# Schematic_RX.net
KiCad netlist of a schematic drawn in Altium Designer
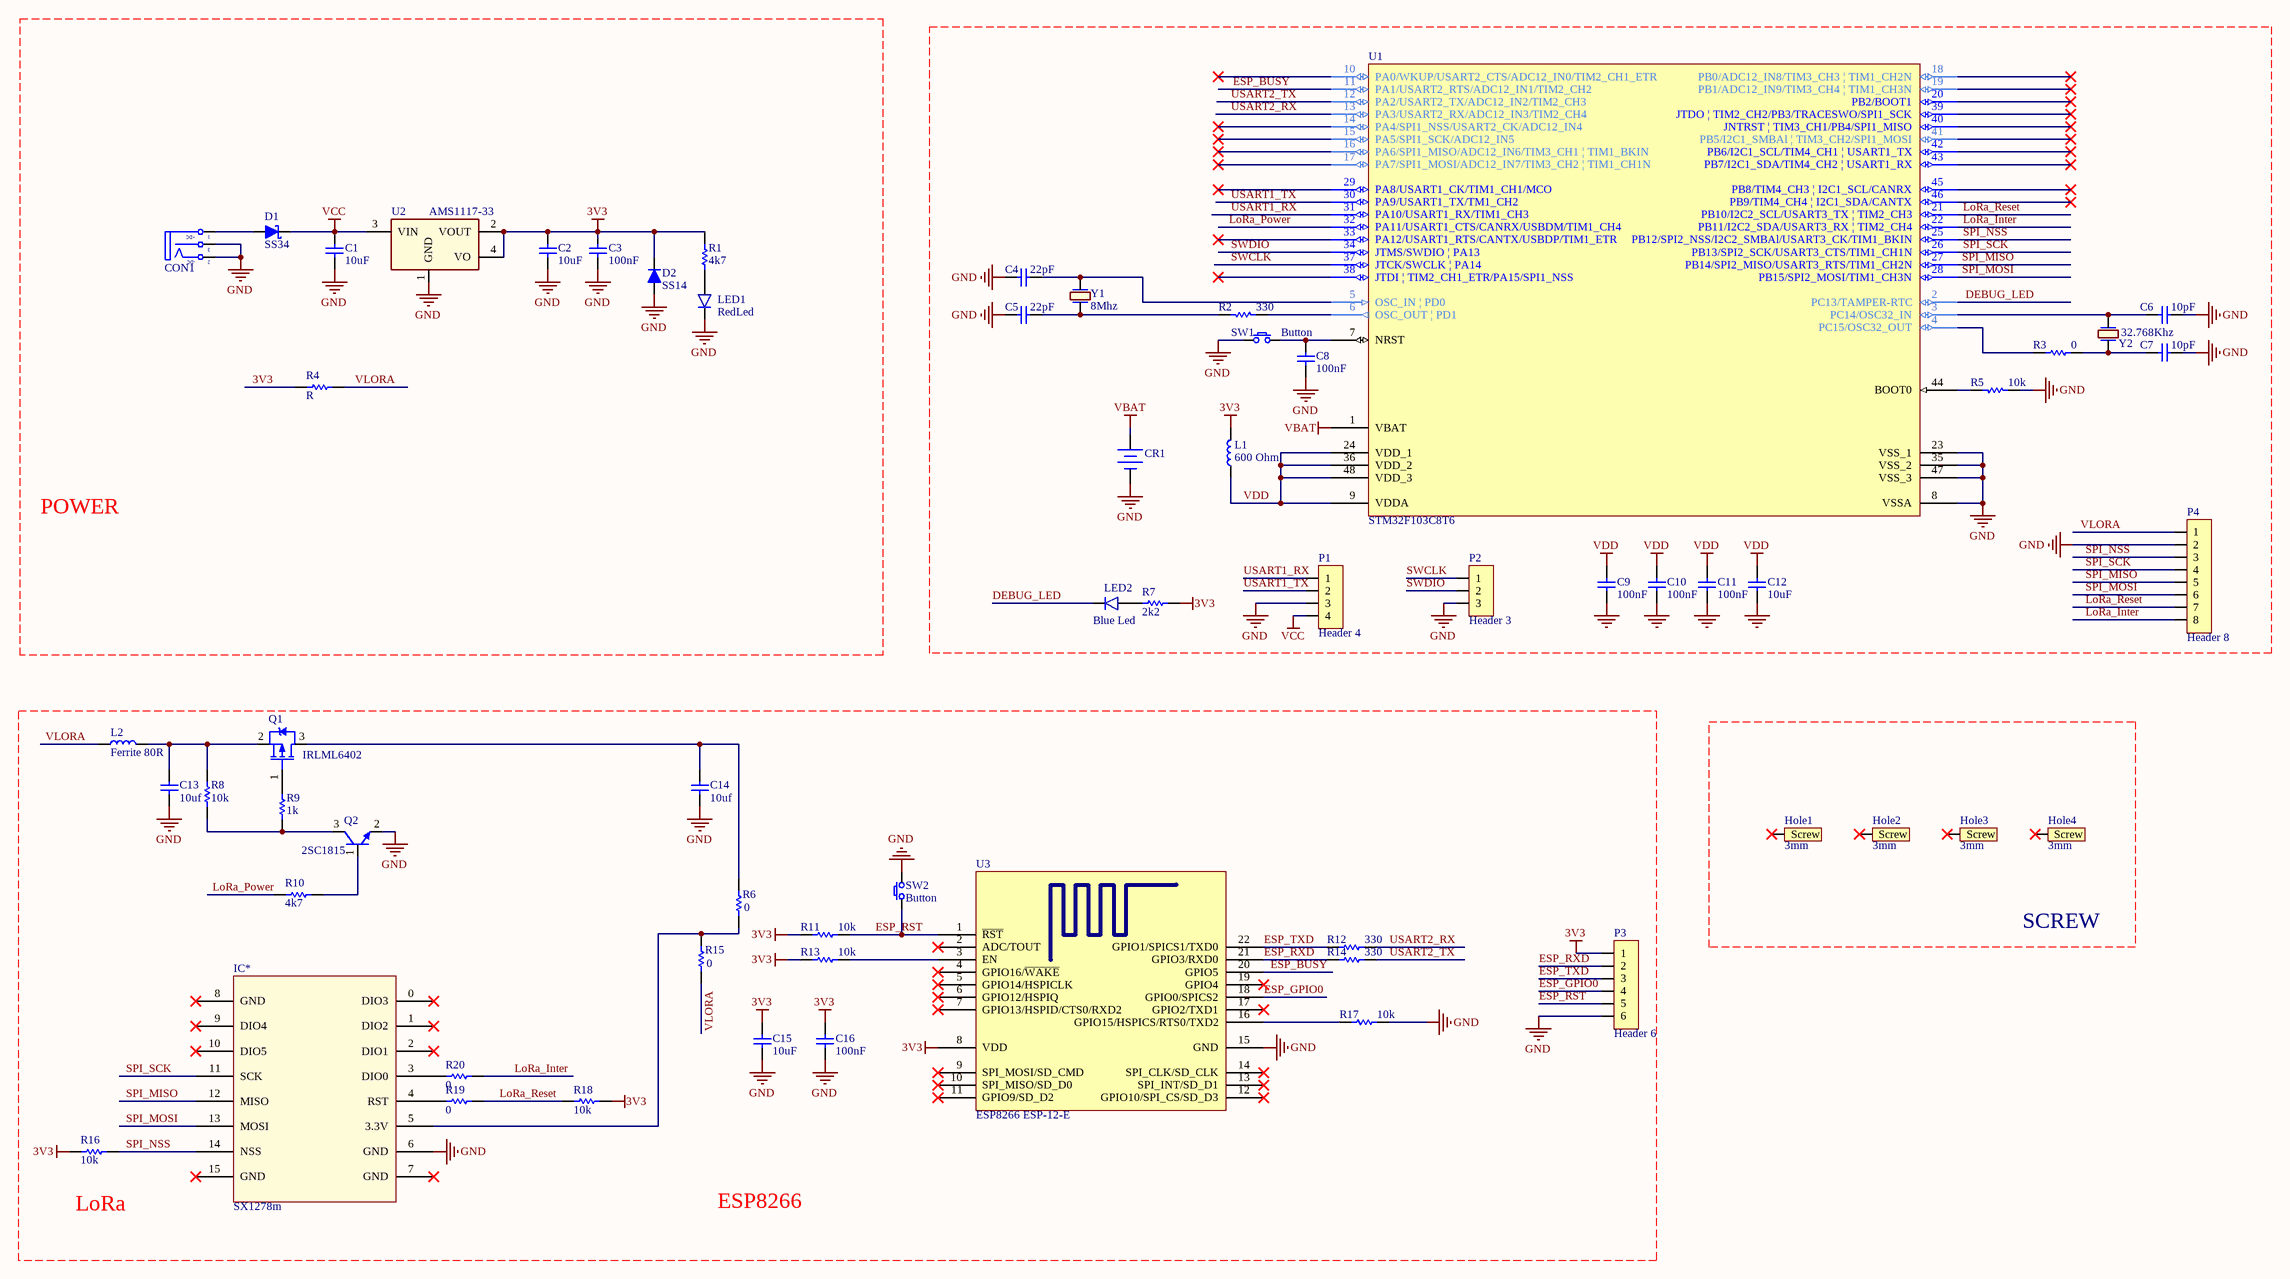
[diagram p0: Schematic_RX.schdoc]

(export (version "E")
  (design (tool "Eeschema 10.0.6"))
  (components
    (comp (ref "C1")
      (value "10uF")
      (footprint "C 0805 (2012)")
      (description "Capacitor non-pol")
      (libsource (lib "BKIT4U_LIB") (part "Capacitor NP"))
    )
    (comp (ref "C2")
      (value "10uF")
      (footprint "C 0805 (2012)")
      (description "Capacitor non-pol")
      (libsource (lib "BKIT4U_LIB") (part "Capacitor NP"))
    )
    (comp (ref "C3")
      (value "100nF")
      (footprint "C 0805 (2012)")
      (description "Capacitor non-pol")
      (libsource (lib "BKIT4U_LIB") (part "Capacitor NP"))
    )
    (comp (ref "C4")
      (value "22pF")
      (footprint "C 0805 (2012)")
      (description "Capacitor non-pol")
      (libsource (lib "BKIT4U_LIB") (part "Capacitor NP"))
    )
    (comp (ref "C5")
      (value "22pF")
      (footprint "C 0805 (2012)")
      (description "Capacitor non-pol")
      (libsource (lib "BKIT4U_LIB") (part "Capacitor NP"))
    )
    (comp (ref "C6")
      (value "10pF")
      (footprint "C 0805 (2012)")
      (description "Capacitor non-pol")
      (libsource (lib "BKIT4U_LIB") (part "Capacitor NP"))
    )
    (comp (ref "C7")
      (value "10pF")
      (footprint "C 0805 (2012)")
      (description "Capacitor non-pol")
      (libsource (lib "BKIT4U_LIB") (part "Capacitor NP"))
    )
    (comp (ref "C8")
      (value "100nF")
      (footprint "C 0805 (2012)")
      (description "Capacitor non-pol")
      (libsource (lib "BKIT4U_LIB") (part "Capacitor NP"))
    )
    (comp (ref "C9")
      (value "100nF")
      (footprint "C 0805 (2012)")
      (description "Capacitor non-pol")
      (libsource (lib "BKIT4U_LIB") (part "Capacitor NP"))
    )
    (comp (ref "C10")
      (value "100nF")
      (footprint "C 0805 (2012)")
      (description "Capacitor non-pol")
      (libsource (lib "BKIT4U_LIB") (part "Capacitor NP"))
    )
    (comp (ref "C11")
      (value "100nF")
      (footprint "C 0805 (2012)")
      (description "Capacitor non-pol")
      (libsource (lib "BKIT4U_LIB") (part "Capacitor NP"))
    )
    (comp (ref "C12")
      (value "10uF")
      (footprint "C 0805 (2012)")
      (description "Capacitor non-pol")
      (libsource (lib "BKIT4U_LIB") (part "Capacitor NP"))
    )
    (comp (ref "C13")
      (value "10uf")
      (footprint "C 0805 (2012)")
      (description "Capacitor non-pol")
      (libsource (lib "BKIT4U_LIB") (part "Capacitor NP"))
    )
    (comp (ref "C14")
      (value "10uf")
      (footprint "C 0805 (2012)")
      (description "Capacitor non-pol")
      (libsource (lib "BKIT4U_LIB") (part "Capacitor NP"))
    )
    (comp (ref "C15")
      (value "10uF")
      (footprint "C 0805 (2012)")
      (description "Capacitor non-pol")
      (libsource (lib "BKIT4U_LIB") (part "Capacitor NP"))
    )
    (comp (ref "C16")
      (value "100nF")
      (footprint "C 0805 (2012)")
      (description "Capacitor non-pol")
      (libsource (lib "BKIT4U_LIB") (part "Capacitor NP"))
    )
    (comp (ref "CON1")
      (value "CON DC PWR")
      (footprint "CON DC-044")
      (description "DC input connector")
      (libsource (lib "BKIT4U_LIB") (part "CON DC PWR"))
    )
    (comp (ref "CR1") (value "~") (footprint "CON CR1220") (libsource (lib "BKIT4U_LIB") (part "Battery")))
    (comp (ref "D1")
      (value "SS34")
      (footprint "DO-214AC (SMA)")
      (description "Schottky Diode")
      (fields (field (name "PUBLISHER") "Altium Limited"))
      (libsource (lib "BKIT4U_LIB") (part "Diode Schottky"))
    )
    (comp (ref "D2")
      (value "SS14")
      (footprint "DO-214AC (SMA)")
      (description "Default Diode")
      (fields (field (name "PUBLISHER") "Altium Limited"))
      (libsource (lib "BKIT4U_LIB") (part "Diode"))
    )
    (comp (ref "Hole1") (value "3mm") (footprint "SCREW/3M/7M") (libsource (lib "BKIT4U_LIB") (part "Screw")))
    (comp (ref "Hole2") (value "3mm") (footprint "SCREW/3M/7M") (libsource (lib "BKIT4U_LIB") (part "Screw")))
    (comp (ref "Hole3") (value "3mm") (footprint "SCREW/3M/7M") (libsource (lib "BKIT4U_LIB") (part "Screw")))
    (comp (ref "Hole4") (value "3mm") (footprint "SCREW/3M/7M") (libsource (lib "BKIT4U_LIB") (part "Screw")))
    (comp (ref "IC*")
      (value "SX1278m")
      (footprint "SX1287m")
      (description "SX1278 - Module LoRa")
      (libsource (lib "SX1278") (part "SX1278m"))
    )
    (comp (ref "L1")
      (value "600 Ohm")
      (footprint "Inductor SMD 0805 (2012)")
      (description "Inductor")
      (libsource (lib "BKIT4U_LIB") (part "Inductor"))
    )
    (comp (ref "L2")
      (value "Ferrite 80R")
      (footprint "Inductor SMD 0805 (2012)")
      (description "Ferrite")
      (libsource (lib "BKIT4U_LIB") (part "Inductor"))
    )
    (comp (ref "LED1")
      (value "RedLed")
      (footprint "Led SMD 0805")
      (description "Typical LED")
      (libsource (lib "BKIT4U_LIB") (part "Led"))
    )
    (comp (ref "LED2")
      (value "Blue Led")
      (footprint "Led SMD 0805")
      (description "Typical LED")
      (libsource (lib "BKIT4U_LIB") (part "Led"))
    )
    (comp (ref "P1")
      (value "Header 4")
      (footprint "CON Header 4")
      (description "Header, 4-Pin")
      (libsource (lib "BKIT4U_LIB") (part "Header 4"))
    )
    (comp (ref "P2")
      (value "Header 3")
      (footprint "Header 3")
      (description "Header, 3-Pin")
      (libsource (lib "BKIT4U_LIB") (part "Header 3"))
    )
    (comp (ref "P3")
      (value "Header 6")
      (footprint "CON Header 6")
      (description "Header, 6-Pin")
      (libsource (lib "BKIT4U_LIB") (part "Header 6"))
    )
    (comp (ref "P4")
      (value "Header 8")
      (footprint "Header 8")
      (description "Header, 8-Pin")
      (fields (field (name "PUBLISHER") "Altium Limited"))
      (libsource (lib "BKIT4U_LIB") (part "Header 8"))
    )
    (comp (ref "Q1")
      (value "IRLML6402")
      (footprint "SOT-23")
      (description "MOSFET P-Channel")
      (libsource (lib "BKIT4U_LIB") (part "MOSFET P-Channel"))
    )
    (comp (ref "Q2")
      (value "2SC1815")
      (footprint "SOT-23")
      (description "NPN Bipolar Transistor")
      (libsource (lib "BKIT4U_LIB") (part "Transistor NPN"))
    )
    (comp (ref "R1")
      (value "4k7")
      (footprint "R 0805 (2012)")
      (description "Resistor")
      (fields (field (name "PUBLISHER") "Altium Limited"))
      (libsource (lib "BKIT4U_LIB") (part "Resistor"))
    )
    (comp (ref "R2")
      (value "330")
      (footprint "R 0805 (2012)")
      (description "Resistor")
      (fields (field (name "PUBLISHER") "Altium Limited"))
      (libsource (lib "BKIT4U_LIB") (part "Resistor"))
    )
    (comp (ref "R3")
      (value "0")
      (footprint "R 0805 (2012)")
      (description "Resistor")
      (fields (field (name "PUBLISHER") "Altium Limited"))
      (libsource (lib "BKIT4U_LIB") (part "Resistor"))
    )
    (comp (ref "R4")
      (value "R")
      (footprint "R 0805 (2012)")
      (description "Resistor")
      (fields (field (name "PUBLISHER") "Altium Limited"))
      (libsource (lib "BKIT4U_LIB") (part "Resistor"))
    )
    (comp (ref "R5")
      (value "10k")
      (footprint "R 0805 (2012)")
      (description "Resistor")
      (fields (field (name "PUBLISHER") "Altium Limited"))
      (libsource (lib "BKIT4U_LIB") (part "Resistor"))
    )
    (comp (ref "R6")
      (value "0")
      (footprint "R 0805 (2012)")
      (description "Resistor")
      (fields (field (name "PUBLISHER") "Altium Limited"))
      (libsource (lib "BKIT4U_LIB") (part "Resistor"))
    )
    (comp (ref "R7")
      (value "2k2")
      (footprint "R 0805 (2012)")
      (description "Resistor")
      (fields (field (name "PUBLISHER") "Altium Limited"))
      (libsource (lib "BKIT4U_LIB") (part "Resistor"))
    )
    (comp (ref "R8")
      (value "10k")
      (footprint "R 0805 (2012)")
      (description "Resistor")
      (fields (field (name "PUBLISHER") "Altium Limited"))
      (libsource (lib "BKIT4U_LIB") (part "Resistor"))
    )
    (comp (ref "R9")
      (value "1k")
      (footprint "R 0805 (2012)")
      (description "Resistor")
      (fields (field (name "PUBLISHER") "Altium Limited"))
      (libsource (lib "BKIT4U_LIB") (part "Resistor"))
    )
    (comp (ref "R10")
      (value "4k7")
      (footprint "R 0805 (2012)")
      (description "Resistor")
      (fields (field (name "PUBLISHER") "Altium Limited"))
      (libsource (lib "BKIT4U_LIB") (part "Resistor"))
    )
    (comp (ref "R11")
      (value "10k")
      (footprint "R 0805 (2012)")
      (description "Resistor")
      (fields (field (name "PUBLISHER") "Altium Limited"))
      (libsource (lib "BKIT4U_LIB") (part "Resistor"))
    )
    (comp (ref "R12")
      (value "330")
      (footprint "R 0805 (2012)")
      (description "Resistor")
      (fields (field (name "PUBLISHER") "Altium Limited"))
      (libsource (lib "BKIT4U_LIB") (part "Resistor"))
    )
    (comp (ref "R13")
      (value "10k")
      (footprint "R 0805 (2012)")
      (description "Resistor")
      (fields (field (name "PUBLISHER") "Altium Limited"))
      (libsource (lib "BKIT4U_LIB") (part "Resistor"))
    )
    (comp (ref "R14")
      (value "330")
      (footprint "R 0805 (2012)")
      (description "Resistor")
      (fields (field (name "PUBLISHER") "Altium Limited"))
      (libsource (lib "BKIT4U_LIB") (part "Resistor"))
    )
    (comp (ref "R15")
      (value "0")
      (footprint "R 0805 (2012)")
      (description "Resistor")
      (fields (field (name "PUBLISHER") "Altium Limited"))
      (libsource (lib "BKIT4U_LIB") (part "Resistor"))
    )
    (comp (ref "R16")
      (value "10k")
      (footprint "R 0805 (2012)")
      (description "Resistor")
      (fields (field (name "PUBLISHER") "Altium Limited"))
      (libsource (lib "BKIT4U_LIB") (part "Resistor"))
    )
    (comp (ref "R17")
      (value "10k")
      (footprint "R 0805 (2012)")
      (description "Resistor")
      (fields (field (name "PUBLISHER") "Altium Limited"))
      (libsource (lib "BKIT4U_LIB") (part "Resistor"))
    )
    (comp (ref "R18")
      (value "10k")
      (footprint "R 0805 (2012)")
      (description "Resistor")
      (fields (field (name "PUBLISHER") "Altium Limited"))
      (libsource (lib "BKIT4U_LIB") (part "Resistor"))
    )
    (comp (ref "R19")
      (value "0")
      (footprint "R 0805 (2012)")
      (description "Resistor")
      (fields (field (name "PUBLISHER") "Altium Limited"))
      (libsource (lib "BKIT4U_LIB") (part "Resistor"))
    )
    (comp (ref "R20")
      (value "0")
      (footprint "R 0805 (2012)")
      (description "Resistor")
      (fields (field (name "PUBLISHER") "Altium Limited"))
      (libsource (lib "BKIT4U_LIB") (part "Resistor"))
    )
    (comp (ref "SW1")
      (value "Button")
      (footprint "SW/2/SMD")
      (description "Tact switch 2 pin")
      (libsource (lib "BKIT4U_LIB") (part "SW SPST"))
    )
    (comp (ref "SW2")
      (value "Button")
      (footprint "SW/2/SMD")
      (description "Tact switch 2 pin")
      (libsource (lib "BKIT4U_LIB") (part "SW SPST"))
    )
    (comp (ref "U1")
      (value "STM32F103C8T6")
      (footprint "LQFP48_N")
      (description "STM32 ARM-based 32-bit MCU with 64 Kbytes Flash, 48-pin LQFP, Industrial Temperature")
      (fields (field (name "PUBLISHER") "Altium Limited"))
      (libsource (lib "BKIT4U_LIB") (part "STM32F103C8T6"))
    )
    (comp (ref "U2")
      (value "AMS1117-33")
      (footprint "SOT-223")
      (description "1A LDO Voltage Regulator, ADJ or fixed 1.5/1.8/2.5/2.85/3.3/5V")
      (libsource (lib "BKIT4U_LIB") (part "AMS1117"))
    )
    (comp (ref "U3")
      (value "ESP8266 ESP-12-E")
      (footprint "ESP8266 ESP-12-E")
      (libsource (lib "ESP8266") (part "ESP8266 ESP-12-E"))
    )
    (comp (ref "Y1")
      (value "8Mhz")
      (footprint "Crystal HC49US SMD")
      (libsource (lib "BKIT4U_LIB") (part "Crystal"))
    )
    (comp (ref "Y2")
      (value "32.768Khz")
      (footprint "Crystal DIP-2")
      (libsource (lib "BKIT4U_LIB") (part "Crystal"))
    )
  )
  (nets
    (net (code "1") (name "/DEBUG_LED") (class "Default")
      (node (ref "LED2") (pin "2") (pinfunction "K_2") (pintype "passive"))
      (node (ref "U1") (pin "2") (pinfunction "PC13/TAMPER-RTC_2") (pintype "bidirectional"))
    )
    (net (code "2") (name "/ESP_BUSY") (class "Default")
      (node (ref "U1") (pin "11") (pinfunction "PA1/USART2_RTS/ADC12_IN1/TIM2_CH2_11") (pintype "bidirectional"))
      (node (ref "U3") (pin "20") (pinfunction "GPIO5_20") (pintype "passive"))
    )
    (net (code "3") (name "/ESP_GPIO0") (class "Default")
      (node (ref "P3") (pin "4") (pinfunction "4_4") (pintype "passive"))
      (node (ref "U3") (pin "18") (pinfunction "GPIO0/SPICS2_18") (pintype "passive"))
    )
    (net (code "4") (name "/ESP_RST") (class "Default")
      (node (ref "P3") (pin "5") (pinfunction "5_5") (pintype "passive"))
      (node (ref "R11") (pin "1") (pinfunction "1_1") (pintype "passive"))
      (node (ref "SW2") (pin "1") (pinfunction "1_1") (pintype "passive"))
      (node (ref "U3") (pin "1") (pinfunction "~{RST}_1") (pintype "passive"))
    )
    (net (code "5") (name "/ESP_RXD") (class "Default")
      (node (ref "P3") (pin "2") (pinfunction "2_2") (pintype "passive"))
      (node (ref "R14") (pin "2") (pinfunction "2_2") (pintype "passive"))
      (node (ref "U3") (pin "21") (pinfunction "GPIO3/RXD0_21") (pintype "passive"))
    )
    (net (code "6") (name "/ESP_TXD") (class "Default")
      (node (ref "P3") (pin "3") (pinfunction "3_3") (pintype "passive"))
      (node (ref "R12") (pin "2") (pinfunction "2_2") (pintype "passive"))
      (node (ref "U3") (pin "22") (pinfunction "GPIO1/SPICS1/TXD0_22") (pintype "passive"))
    )
    (net (code "7") (name "/LoRa_Inter") (class "Default")
      (node (ref "P4") (pin "8") (pinfunction "8_8") (pintype "passive"))
      (node (ref "R20") (pin "2") (pinfunction "2_2") (pintype "passive"))
      (node (ref "U1") (pin "22") (pinfunction "PB11/I2C2_SDA/USART3_RX_¦_TIM2_CH4_22") (pintype "bidirectional"))
    )
    (net (code "8") (name "/LoRa_Power") (class "Default")
      (node (ref "R10") (pin "1") (pinfunction "1_1") (pintype "passive"))
      (node (ref "U1") (pin "32") (pinfunction "PA11/USART1_CTS/CANRX/USBDM/TIM1_CH4_32") (pintype "bidirectional"))
    )
    (net (code "9") (name "/LoRa_Reset") (class "Default")
      (node (ref "P4") (pin "7") (pinfunction "7_7") (pintype "passive"))
      (node (ref "R18") (pin "2") (pinfunction "2_2") (pintype "passive"))
      (node (ref "R19") (pin "2") (pinfunction "2_2") (pintype "passive"))
      (node (ref "U1") (pin "21") (pinfunction "PB10/I2C2_SCL/USART3_TX_¦_TIM2_CH3_21") (pintype "bidirectional"))
    )
    (net (code "10") (name "/SPI_MISO") (class "Default")
      (node (ref "IC*") (pin "12") (pinfunction "MISO_12") (pintype "passive"))
      (node (ref "P4") (pin "5") (pinfunction "5_5") (pintype "passive"))
      (node (ref "U1") (pin "27") (pinfunction "PB14/SPI2_MISO/USART3_RTS/TIM1_CH2N_27") (pintype "bidirectional"))
    )
    (net (code "11") (name "/SPI_MOSI") (class "Default")
      (node (ref "IC*") (pin "13") (pinfunction "MOSI_13") (pintype "passive"))
      (node (ref "P4") (pin "6") (pinfunction "6_6") (pintype "passive"))
      (node (ref "U1") (pin "28") (pinfunction "PB15/SPI2_MOSI/TIM1_CH3N_28") (pintype "bidirectional"))
    )
    (net (code "12") (name "/SPI_NSS") (class "Default")
      (node (ref "IC*") (pin "14") (pinfunction "NSS_14") (pintype "passive"))
      (node (ref "P4") (pin "3") (pinfunction "3_3") (pintype "passive"))
      (node (ref "R16") (pin "2") (pinfunction "2_2") (pintype "passive"))
      (node (ref "U1") (pin "25") (pinfunction "PB12/SPI2_NSS/I2C2_SMBAl/USART3_CK/TIM1_BKIN_25") (pintype "bidirectional"))
    )
    (net (code "13") (name "/SPI_SCK") (class "Default")
      (node (ref "IC*") (pin "11") (pinfunction "SCK_11") (pintype "passive"))
      (node (ref "P4") (pin "4") (pinfunction "4_4") (pintype "passive"))
      (node (ref "U1") (pin "26") (pinfunction "PB13/SPI2_SCK/USART3_CTS/TIM1_CH1N_26") (pintype "bidirectional"))
    )
    (net (code "14") (name "/SWCLK") (class "Default")
      (node (ref "P2") (pin "1") (pinfunction "1_1") (pintype "passive"))
      (node (ref "U1") (pin "37") (pinfunction "JTCK/SWCLK_¦_PA14_37") (pintype "bidirectional"))
    )
    (net (code "15") (name "/SWDIO") (class "Default")
      (node (ref "P2") (pin "2") (pinfunction "2_2") (pintype "passive"))
      (node (ref "U1") (pin "34") (pinfunction "JTMS/SWDIO_¦_PA13_34") (pintype "bidirectional"))
    )
    (net (code "16") (name "/USART1_RX") (class "Default")
      (node (ref "P1") (pin "1") (pinfunction "1_1") (pintype "passive"))
      (node (ref "U1") (pin "31") (pinfunction "PA10/USART1_RX/TIM1_CH3_31") (pintype "bidirectional"))
    )
    (net (code "17") (name "/USART1_TX") (class "Default")
      (node (ref "P1") (pin "2") (pinfunction "2_2") (pintype "passive"))
      (node (ref "U1") (pin "30") (pinfunction "PA9/USART1_TX/TM1_CH2_30") (pintype "bidirectional"))
    )
    (net (code "18") (name "/USART2_RX") (class "Default")
      (node (ref "R12") (pin "1") (pinfunction "1_1") (pintype "passive"))
      (node (ref "U1") (pin "13") (pinfunction "PA3/USART2_RX/ADC12_IN3/TIM2_CH4_13") (pintype "bidirectional"))
    )
    (net (code "19") (name "/USART2_TX") (class "Default")
      (node (ref "R14") (pin "1") (pinfunction "1_1") (pintype "passive"))
      (node (ref "U1") (pin "12") (pinfunction "PA2/USART2_TX/ADC12_IN2/TIM2_CH3_12") (pintype "bidirectional"))
    )
    (net (code "20") (name "/VLORA") (class "Default")
      (node (ref "L2") (pin "1") (pinfunction "1_1") (pintype "passive"))
      (node (ref "P4") (pin "1") (pinfunction "1_1") (pintype "passive"))
      (node (ref "R15") (pin "1") (pinfunction "1_1") (pintype "passive"))
      (node (ref "R4") (pin "2") (pinfunction "2_2") (pintype "passive"))
    )
    (net (code "21") (name "3V3") (class "Default")
      (node (ref "C15") (pin "1") (pinfunction "1_1") (pintype "passive"))
      (node (ref "C16") (pin "1") (pinfunction "1_1") (pintype "passive"))
      (node (ref "C2") (pin "1") (pinfunction "1_1") (pintype "passive"))
      (node (ref "C3") (pin "1") (pinfunction "1_1") (pintype "passive"))
      (node (ref "D2") (pin "2") (pinfunction "K_2") (pintype "passive"))
      (node (ref "L1") (pin "2") (pinfunction "2_2") (pintype "passive"))
      (node (ref "P3") (pin "1") (pinfunction "1_1") (pintype "passive"))
      (node (ref "R1") (pin "1") (pinfunction "1_1") (pintype "passive"))
      (node (ref "R11") (pin "2") (pinfunction "2_2") (pintype "passive"))
      (node (ref "R13") (pin "2") (pinfunction "2_2") (pintype "passive"))
      (node (ref "R16") (pin "1") (pinfunction "1_1") (pintype "passive"))
      (node (ref "R18") (pin "1") (pinfunction "1_1") (pintype "passive"))
      (node (ref "R4") (pin "1") (pinfunction "1_1") (pintype "passive"))
      (node (ref "R7") (pin "2") (pinfunction "2_2") (pintype "passive"))
      (node (ref "U2") (pin "2") (pinfunction "VOUT_2") (pintype "passive"))
      (node (ref "U2") (pin "4") (pinfunction "VO_4") (pintype "passive"))
      (node (ref "U3") (pin "8") (pinfunction "VDD_8") (pintype "passive"))
    )
    (net (code "22") (name "GND") (class "Default")
      (node (ref "C1") (pin "2") (pinfunction "2_2") (pintype "passive"))
      (node (ref "C10") (pin "2") (pinfunction "2_2") (pintype "passive"))
      (node (ref "C11") (pin "2") (pinfunction "2_2") (pintype "passive"))
      (node (ref "C12") (pin "2") (pinfunction "2_2") (pintype "passive"))
      (node (ref "C13") (pin "2") (pinfunction "2_2") (pintype "passive"))
      (node (ref "C14") (pin "2") (pinfunction "2_2") (pintype "passive"))
      (node (ref "C15") (pin "2") (pinfunction "2_2") (pintype "passive"))
      (node (ref "C16") (pin "2") (pinfunction "2_2") (pintype "passive"))
      (node (ref "C2") (pin "2") (pinfunction "2_2") (pintype "passive"))
      (node (ref "C3") (pin "2") (pinfunction "2_2") (pintype "passive"))
      (node (ref "C4") (pin "2") (pinfunction "2_2") (pintype "passive"))
      (node (ref "C5") (pin "2") (pinfunction "2_2") (pintype "passive"))
      (node (ref "C6") (pin "2") (pinfunction "2_2") (pintype "passive"))
      (node (ref "C7") (pin "2") (pinfunction "2_2") (pintype "passive"))
      (node (ref "C8") (pin "2") (pinfunction "2_2") (pintype "passive"))
      (node (ref "C9") (pin "2") (pinfunction "2_2") (pintype "passive"))
      (node (ref "CON1") (pin "2") (pinfunction "TN_2") (pintype "passive"))
      (node (ref "CON1") (pin "3") (pinfunction "S_3") (pintype "power_in"))
      (node (ref "CR1") (pin "2") (pinfunction "GND_2") (pintype "passive"))
      (node (ref "D2") (pin "1") (pinfunction "A_1") (pintype "passive"))
      (node (ref "IC*") (pin "6") (pinfunction "GND_6") (pintype "passive"))
      (node (ref "LED1") (pin "2") (pinfunction "K_2") (pintype "passive"))
      (node (ref "P1") (pin "3") (pinfunction "3_3") (pintype "passive"))
      (node (ref "P2") (pin "3") (pinfunction "3_3") (pintype "passive"))
      (node (ref "P3") (pin "6") (pinfunction "6_6") (pintype "passive"))
      (node (ref "P4") (pin "2") (pinfunction "2_2") (pintype "passive"))
      (node (ref "Q2") (pin "2") (pinfunction "E_2") (pintype "passive"))
      (node (ref "R17") (pin "1") (pinfunction "1_1") (pintype "passive"))
      (node (ref "R5") (pin "1") (pinfunction "1_1") (pintype "passive"))
      (node (ref "SW1") (pin "1") (pinfunction "1_1") (pintype "passive"))
      (node (ref "SW2") (pin "2") (pinfunction "2_2") (pintype "passive"))
      (node (ref "U1") (pin "23") (pinfunction "VSS_1_23") (pintype "power_in"))
      (node (ref "U1") (pin "35") (pinfunction "VSS_2_35") (pintype "power_in"))
      (node (ref "U1") (pin "47") (pinfunction "VSS_3_47") (pintype "power_in"))
      (node (ref "U1") (pin "8") (pinfunction "VSSA_8") (pintype "power_in"))
      (node (ref "U2") (pin "1") (pinfunction "GND_1") (pintype "passive"))
      (node (ref "U3") (pin "15") (pinfunction "GND_15") (pintype "passive"))
    )
    (net (code "23") (name "Net-(C5-Pad1)") (class "Default")
      (node (ref "C5") (pin "1") (pinfunction "1_1") (pintype "passive"))
      (node (ref "R2") (pin "2") (pinfunction "2_2") (pintype "passive"))
      (node (ref "Y1") (pin "1") (pinfunction "1_1") (pintype "passive"))
    )
    (net (code "24") (name "Net-(C7-Pad1)") (class "Default")
      (node (ref "C7") (pin "1") (pinfunction "1_1") (pintype "passive"))
      (node (ref "R3") (pin "2") (pinfunction "2_2") (pintype "passive"))
      (node (ref "Y2") (pin "1") (pinfunction "1_1") (pintype "passive"))
    )
    (net (code "25") (name "Net-(CON1-T)") (class "Default")
      (node (ref "CON1") (pin "1") (pinfunction "T_1") (pintype "passive"))
      (node (ref "D1") (pin "1") (pinfunction "A_1") (pintype "passive"))
    )
    (net (code "26") (name "Net-(IC*-3.3V)") (class "Default")
      (node (ref "IC*") (pin "5") (pinfunction "3.3V_5") (pintype "passive"))
      (node (ref "R15") (pin "2") (pinfunction "2_2") (pintype "passive"))
      (node (ref "R6") (pin "1") (pinfunction "1_1") (pintype "passive"))
    )
    (net (code "27") (name "Net-(IC*-DIO0)") (class "Default")
      (node (ref "IC*") (pin "3") (pinfunction "DIO0_3") (pintype "passive"))
      (node (ref "R20") (pin "1") (pinfunction "1_1") (pintype "passive"))
    )
    (net (code "28") (name "Net-(IC*-RST)") (class "Default")
      (node (ref "IC*") (pin "4") (pinfunction "RST_4") (pintype "passive"))
      (node (ref "R19") (pin "1") (pinfunction "1_1") (pintype "passive"))
    )
    (net (code "29") (name "Net-(LED1-A)") (class "Default")
      (node (ref "LED1") (pin "1") (pinfunction "A_1") (pintype "passive"))
      (node (ref "R1") (pin "2") (pinfunction "2_2") (pintype "passive"))
    )
    (net (code "30") (name "Net-(LED2-A)") (class "Default")
      (node (ref "LED2") (pin "1") (pinfunction "A_1") (pintype "passive"))
      (node (ref "R7") (pin "1") (pinfunction "1_1") (pintype "passive"))
    )
    (net (code "31") (name "Net-(Q1-D)") (class "Default")
      (node (ref "C14") (pin "1") (pinfunction "1_1") (pintype "passive"))
      (node (ref "Q1") (pin "3") (pinfunction "D_3") (pintype "passive"))
      (node (ref "R6") (pin "2") (pinfunction "2_2") (pintype "passive"))
    )
    (net (code "32") (name "Net-(Q1-G)") (class "Default")
      (node (ref "Q1") (pin "1") (pinfunction "G_1") (pintype "passive"))
      (node (ref "R9") (pin "2") (pinfunction "2_2") (pintype "passive"))
    )
    (net (code "33") (name "Net-(Q1-S)") (class "Default")
      (node (ref "C13") (pin "1") (pinfunction "1_1") (pintype "passive"))
      (node (ref "L2") (pin "2") (pinfunction "2_2") (pintype "passive"))
      (node (ref "Q1") (pin "2") (pinfunction "S_2") (pintype "passive"))
      (node (ref "R8") (pin "2") (pinfunction "2_2") (pintype "passive"))
    )
    (net (code "34") (name "Net-(Q2-B)") (class "Default")
      (node (ref "Q2") (pin "1") (pinfunction "B_1") (pintype "passive"))
      (node (ref "R10") (pin "2") (pinfunction "2_2") (pintype "passive"))
    )
    (net (code "35") (name "Net-(Q2-C)") (class "Default")
      (node (ref "Q2") (pin "3") (pinfunction "C_3") (pintype "passive"))
      (node (ref "R8") (pin "1") (pinfunction "1_1") (pintype "passive"))
      (node (ref "R9") (pin "1") (pinfunction "1_1") (pintype "passive"))
    )
    (net (code "36") (name "Net-(U1-BOOT0)") (class "Default")
      (node (ref "R5") (pin "2") (pinfunction "2_2") (pintype "passive"))
      (node (ref "U1") (pin "44") (pinfunction "BOOT0_44") (pintype "input"))
    )
    (net (code "37") (name "Net-(U1-NRST)") (class "Default")
      (node (ref "C8") (pin "1") (pinfunction "1_1") (pintype "passive"))
      (node (ref "SW1") (pin "2") (pinfunction "2_2") (pintype "passive"))
      (node (ref "U1") (pin "7") (pinfunction "NRST_7") (pintype "bidirectional"))
    )
    (net (code "38") (name "Net-(U1-OSC_IN_¦_PD0)") (class "Default")
      (node (ref "C4") (pin "1") (pinfunction "1_1") (pintype "passive"))
      (node (ref "U1") (pin "5") (pinfunction "OSC_IN_¦_PD0_5") (pintype "input"))
      (node (ref "Y1") (pin "2") (pinfunction "2_2") (pintype "passive"))
    )
    (net (code "39") (name "Net-(U1-OSC_OUT_¦_PD1)") (class "Default")
      (node (ref "R2") (pin "1") (pinfunction "1_1") (pintype "passive"))
      (node (ref "U1") (pin "6") (pinfunction "OSC_OUT_¦_PD1_6") (pintype "output"))
    )
    (net (code "40") (name "Net-(U1-PC14{slash}OSC32_IN)") (class "Default")
      (node (ref "C6") (pin "1") (pinfunction "1_1") (pintype "passive"))
      (node (ref "U1") (pin "3") (pinfunction "PC14/OSC32_IN_3") (pintype "bidirectional"))
      (node (ref "Y2") (pin "2") (pinfunction "2_2") (pintype "passive"))
    )
    (net (code "41") (name "Net-(U1-PC15{slash}OSC32_OUT)") (class "Default")
      (node (ref "R3") (pin "1") (pinfunction "1_1") (pintype "passive"))
      (node (ref "U1") (pin "4") (pinfunction "PC15/OSC32_OUT_4") (pintype "bidirectional"))
    )
    (net (code "42") (name "Net-(U3-EN)") (class "Default")
      (node (ref "R13") (pin "1") (pinfunction "1_1") (pintype "passive"))
      (node (ref "U3") (pin "3") (pinfunction "EN_3") (pintype "passive"))
    )
    (net (code "43") (name "Net-(U3-GPIO15{slash}HSPICS{slash}RTS0{slash}TXD2)") (class "Default")
      (node (ref "R17") (pin "2") (pinfunction "2_2") (pintype "passive"))
      (node (ref "U3") (pin "16") (pinfunction "GPIO15/HSPICS/RTS0/TXD2_16") (pintype "passive"))
    )
    (net (code "44") (name "VBAT") (class "Default")
      (node (ref "CR1") (pin "1") (pinfunction "VCC_1") (pintype "passive"))
      (node (ref "U1") (pin "1") (pinfunction "VBAT_1") (pintype "power_in"))
    )
    (net (code "45") (name "VCC") (class "Default")
      (node (ref "C1") (pin "1") (pinfunction "1_1") (pintype "passive"))
      (node (ref "D1") (pin "2") (pinfunction "K_2") (pintype "passive"))
      (node (ref "P1") (pin "4") (pinfunction "4_4") (pintype "passive"))
      (node (ref "U2") (pin "3") (pinfunction "VIN_3") (pintype "power_in"))
    )
    (net (code "46") (name "VDD") (class "Default")
      (node (ref "C10") (pin "1") (pinfunction "1_1") (pintype "passive"))
      (node (ref "C11") (pin "1") (pinfunction "1_1") (pintype "passive"))
      (node (ref "C12") (pin "1") (pinfunction "1_1") (pintype "passive"))
      (node (ref "C9") (pin "1") (pinfunction "1_1") (pintype "passive"))
      (node (ref "L1") (pin "1") (pinfunction "1_1") (pintype "passive"))
      (node (ref "U1") (pin "24") (pinfunction "VDD_1_24") (pintype "power_in"))
      (node (ref "U1") (pin "36") (pinfunction "VDD_2_36") (pintype "power_in"))
      (node (ref "U1") (pin "48") (pinfunction "VDD_3_48") (pintype "power_in"))
      (node (ref "U1") (pin "9") (pinfunction "VDDA_9") (pintype "power_in"))
    )
    (net (code "47") (name "unconnected-(Hole1-Screw-Pad1)") (class "Default")
      (node (ref "Hole1") (pin "1") (pinfunction "Screw_1") (pintype "passive+no_connect"))
    )
    (net (code "48") (name "unconnected-(Hole2-Screw-Pad1)") (class "Default")
      (node (ref "Hole2") (pin "1") (pinfunction "Screw_1") (pintype "passive+no_connect"))
    )
    (net (code "49") (name "unconnected-(Hole3-Screw-Pad1)") (class "Default")
      (node (ref "Hole3") (pin "1") (pinfunction "Screw_1") (pintype "passive+no_connect"))
    )
    (net (code "50") (name "unconnected-(Hole4-Screw-Pad1)") (class "Default")
      (node (ref "Hole4") (pin "1") (pinfunction "Screw_1") (pintype "passive+no_connect"))
    )
    (net (code "51") (name "unconnected-(IC*-DIO1-Pad2)") (class "Default")
      (node (ref "IC*") (pin "2") (pinfunction "DIO1_2") (pintype "passive+no_connect"))
    )
    (net (code "52") (name "unconnected-(IC*-DIO2-Pad1)") (class "Default")
      (node (ref "IC*") (pin "1") (pinfunction "DIO2_1") (pintype "passive+no_connect"))
    )
    (net (code "53") (name "unconnected-(IC*-DIO3-Pad0)") (class "Default")
      (node (ref "IC*") (pin "0") (pinfunction "DIO3_0") (pintype "passive+no_connect"))
    )
    (net (code "54") (name "unconnected-(IC*-DIO4-Pad9)") (class "Default")
      (node (ref "IC*") (pin "9") (pinfunction "DIO4_9") (pintype "passive+no_connect"))
    )
    (net (code "55") (name "unconnected-(IC*-DIO5-Pad10)") (class "Default")
      (node (ref "IC*") (pin "10") (pinfunction "DIO5_10") (pintype "passive+no_connect"))
    )
    (net (code "56") (name "unconnected-(IC*-GND-Pad7)") (class "Default")
      (node (ref "IC*") (pin "7") (pinfunction "GND_7") (pintype "passive+no_connect"))
    )
    (net (code "57") (name "unconnected-(IC*-GND-Pad8)") (class "Default")
      (node (ref "IC*") (pin "8") (pinfunction "GND_8") (pintype "passive+no_connect"))
    )
    (net (code "58") (name "unconnected-(IC*-GND-Pad15)") (class "Default")
      (node (ref "IC*") (pin "15") (pinfunction "GND_15") (pintype "passive+no_connect"))
    )
    (net (code "59") (name "unconnected-(U1-JNTRST_¦_TIM3_CH1{slash}PB4{slash}SPI1_MISO-Pad40)") (class "Default")
      (node (ref "U1") (pin "40") (pinfunction "JNTRST_¦_TIM3_CH1/PB4/SPI1_MISO_40") (pintype "bidirectional+no_connect"))
    )
    (net (code "60") (name "unconnected-(U1-JTDI_¦_TIM2_CH1_ETR{slash}PA15{slash}SPI1_NSS-Pad38)") (class "Default")
      (node (ref "U1") (pin "38") (pinfunction "JTDI_¦_TIM2_CH1_ETR/PA15/SPI1_NSS_38") (pintype "bidirectional+no_connect"))
    )
    (net (code "61") (name "unconnected-(U1-JTDO_¦_TIM2_CH2{slash}PB3{slash}TRACESWO{slash}SPI1_SCK-Pad39)") (class "Default")
      (node (ref "U1") (pin "39") (pinfunction "JTDO_¦_TIM2_CH2/PB3/TRACESWO/SPI1_SCK_39") (pintype "bidirectional+no_connect"))
    )
    (net (code "62") (name "unconnected-(U1-PA0{slash}WKUP{slash}USART2_CTS{slash}ADC12_IN0{slash}TIM2_CH1_ETR-Pad10)") (class "Default")
      (node (ref "U1") (pin "10") (pinfunction "PA0/WKUP/USART2_CTS/ADC12_IN0/TIM2_CH1_ETR_10") (pintype "bidirectional+no_connect"))
    )
    (net (code "63") (name "unconnected-(U1-PA4{slash}SPI1_NSS{slash}USART2_CK{slash}ADC12_IN4-Pad14)") (class "Default")
      (node (ref "U1") (pin "14") (pinfunction "PA4/SPI1_NSS/USART2_CK/ADC12_IN4_14") (pintype "bidirectional+no_connect"))
    )
    (net (code "64") (name "unconnected-(U1-PA5{slash}SPI1_SCK{slash}ADC12_IN5-Pad15)") (class "Default")
      (node (ref "U1") (pin "15") (pinfunction "PA5/SPI1_SCK/ADC12_IN5_15") (pintype "bidirectional+no_connect"))
    )
    (net (code "65") (name "unconnected-(U1-PA6{slash}SPI1_MISO{slash}ADC12_IN6{slash}TIM3_CH1_¦_TIM1_BKIN-Pad16)") (class "Default")
      (node (ref "U1") (pin "16") (pinfunction "PA6/SPI1_MISO/ADC12_IN6/TIM3_CH1_¦_TIM1_BKIN_16") (pintype "bidirectional+no_connect"))
    )
    (net (code "66") (name "unconnected-(U1-PA7{slash}SPI1_MOSI{slash}ADC12_IN7{slash}TIM3_CH2_¦_TIM1_CH1N-Pad17)") (class "Default")
      (node (ref "U1") (pin "17") (pinfunction "PA7/SPI1_MOSI/ADC12_IN7/TIM3_CH2_¦_TIM1_CH1N_17") (pintype "bidirectional+no_connect"))
    )
    (net (code "67") (name "unconnected-(U1-PA8{slash}USART1_CK{slash}TIM1_CH1{slash}MCO-Pad29)") (class "Default")
      (node (ref "U1") (pin "29") (pinfunction "PA8/USART1_CK/TIM1_CH1/MCO_29") (pintype "bidirectional+no_connect"))
    )
    (net (code "68") (name "unconnected-(U1-PA12{slash}USART1_RTS{slash}CANTX{slash}USBDP{slash}TIM1_ETR-Pad33)") (class "Default")
      (node (ref "U1") (pin "33") (pinfunction "PA12/USART1_RTS/CANTX/USBDP/TIM1_ETR_33") (pintype "bidirectional+no_connect"))
    )
    (net (code "69") (name "unconnected-(U1-PB0{slash}ADC12_IN8{slash}TIM3_CH3_¦_TIM1_CH2N-Pad18)") (class "Default")
      (node (ref "U1") (pin "18") (pinfunction "PB0/ADC12_IN8/TIM3_CH3_¦_TIM1_CH2N_18") (pintype "bidirectional+no_connect"))
    )
    (net (code "70") (name "unconnected-(U1-PB1{slash}ADC12_IN9{slash}TIM3_CH4_¦_TIM1_CH3N-Pad19)") (class "Default")
      (node (ref "U1") (pin "19") (pinfunction "PB1/ADC12_IN9/TIM3_CH4_¦_TIM1_CH3N_19") (pintype "bidirectional+no_connect"))
    )
    (net (code "71") (name "unconnected-(U1-PB2{slash}BOOT1-Pad20)") (class "Default")
      (node (ref "U1") (pin "20") (pinfunction "PB2/BOOT1_20") (pintype "bidirectional+no_connect"))
    )
    (net (code "72") (name "unconnected-(U1-PB5{slash}I2C1_SMBAl_¦_TIM3_CH2{slash}SPI1_MOSI-Pad41)") (class "Default")
      (node (ref "U1") (pin "41") (pinfunction "PB5/I2C1_SMBAl_¦_TIM3_CH2/SPI1_MOSI_41") (pintype "bidirectional+no_connect"))
    )
    (net (code "73") (name "unconnected-(U1-PB6{slash}I2C1_SCL{slash}TIM4_CH1_¦_USART1_TX-Pad42)") (class "Default")
      (node (ref "U1") (pin "42") (pinfunction "PB6/I2C1_SCL/TIM4_CH1_¦_USART1_TX_42") (pintype "bidirectional+no_connect"))
    )
    (net (code "74") (name "unconnected-(U1-PB7{slash}I2C1_SDA{slash}TIM4_CH2_¦_USART1_RX-Pad43)") (class "Default")
      (node (ref "U1") (pin "43") (pinfunction "PB7/I2C1_SDA/TIM4_CH2_¦_USART1_RX_43") (pintype "bidirectional+no_connect"))
    )
    (net (code "75") (name "unconnected-(U1-PB8{slash}TIM4_CH3_¦_I2C1_SCL{slash}CANRX-Pad45)") (class "Default")
      (node (ref "U1") (pin "45") (pinfunction "PB8/TIM4_CH3_¦_I2C1_SCL/CANRX_45") (pintype "bidirectional+no_connect"))
    )
    (net (code "76") (name "unconnected-(U1-PB9{slash}TIM4_CH4_¦_I2C1_SDA{slash}CANTX-Pad46)") (class "Default")
      (node (ref "U1") (pin "46") (pinfunction "PB9/TIM4_CH4_¦_I2C1_SDA/CANTX_46") (pintype "bidirectional+no_connect"))
    )
    (net (code "77") (name "unconnected-(U3-ADC{slash}TOUT-Pad2)") (class "Default")
      (node (ref "U3") (pin "2") (pinfunction "ADC/TOUT_2") (pintype "passive+no_connect"))
    )
    (net (code "78") (name "unconnected-(U3-GPIO2{slash}TXD1-Pad17)") (class "Default")
      (node (ref "U3") (pin "17") (pinfunction "GPIO2/TXD1_17") (pintype "passive+no_connect"))
    )
    (net (code "79") (name "unconnected-(U3-GPIO4-Pad19)") (class "Default")
      (node (ref "U3") (pin "19") (pinfunction "GPIO4_19") (pintype "passive+no_connect"))
    )
    (net (code "80") (name "unconnected-(U3-GPIO9{slash}SD_D2-Pad11)") (class "Default")
      (node (ref "U3") (pin "11") (pinfunction "GPIO9/SD_D2_11") (pintype "passive+no_connect"))
    )
    (net (code "81") (name "unconnected-(U3-GPIO10{slash}SPI_CS{slash}SD_D3-Pad12)") (class "Default")
      (node (ref "U3") (pin "12") (pinfunction "GPIO10/SPI_CS/SD_D3_12") (pintype "passive+no_connect"))
    )
    (net (code "82") (name "unconnected-(U3-GPIO12{slash}HSPIQ-Pad6)") (class "Default")
      (node (ref "U3") (pin "6") (pinfunction "GPIO12/HSPIQ_6") (pintype "passive+no_connect"))
    )
    (net (code "83") (name "unconnected-(U3-GPIO13{slash}HSPID{slash}CTS0{slash}RXD2-Pad7)") (class "Default")
      (node (ref "U3") (pin "7") (pinfunction "GPIO13/HSPID/CTS0/RXD2_7") (pintype "passive+no_connect"))
    )
    (net (code "84") (name "unconnected-(U3-GPIO14{slash}HSPICLK-Pad5)") (class "Default")
      (node (ref "U3") (pin "5") (pinfunction "GPIO14/HSPICLK_5") (pintype "passive+no_connect"))
    )
    (net (code "85") (name "unconnected-(U3-GPIO16{slash}~{WAKE}-Pad4)") (class "Default")
      (node (ref "U3") (pin "4") (pinfunction "GPIO16/~{WAKE}_4") (pintype "passive+no_connect"))
    )
    (net (code "86") (name "unconnected-(U3-SPI_CLK{slash}SD_CLK-Pad14)") (class "Default")
      (node (ref "U3") (pin "14") (pinfunction "SPI_CLK/SD_CLK_14") (pintype "passive+no_connect"))
    )
    (net (code "87") (name "unconnected-(U3-SPI_INT{slash}SD_D1-Pad13)") (class "Default")
      (node (ref "U3") (pin "13") (pinfunction "SPI_INT/SD_D1_13") (pintype "passive+no_connect"))
    )
    (net (code "88") (name "unconnected-(U3-SPI_MISO{slash}SD_D0-Pad10)") (class "Default")
      (node (ref "U3") (pin "10") (pinfunction "SPI_MISO/SD_D0_10") (pintype "passive+no_connect"))
    )
    (net (code "89") (name "unconnected-(U3-SPI_MOSI{slash}SD_CMD-Pad9)") (class "Default")
      (node (ref "U3") (pin "9") (pinfunction "SPI_MOSI/SD_CMD_9") (pintype "passive+no_connect"))
    )
  )
)
